# Debug.net
KiCad netlist of a schematic drawn in Altium Designer
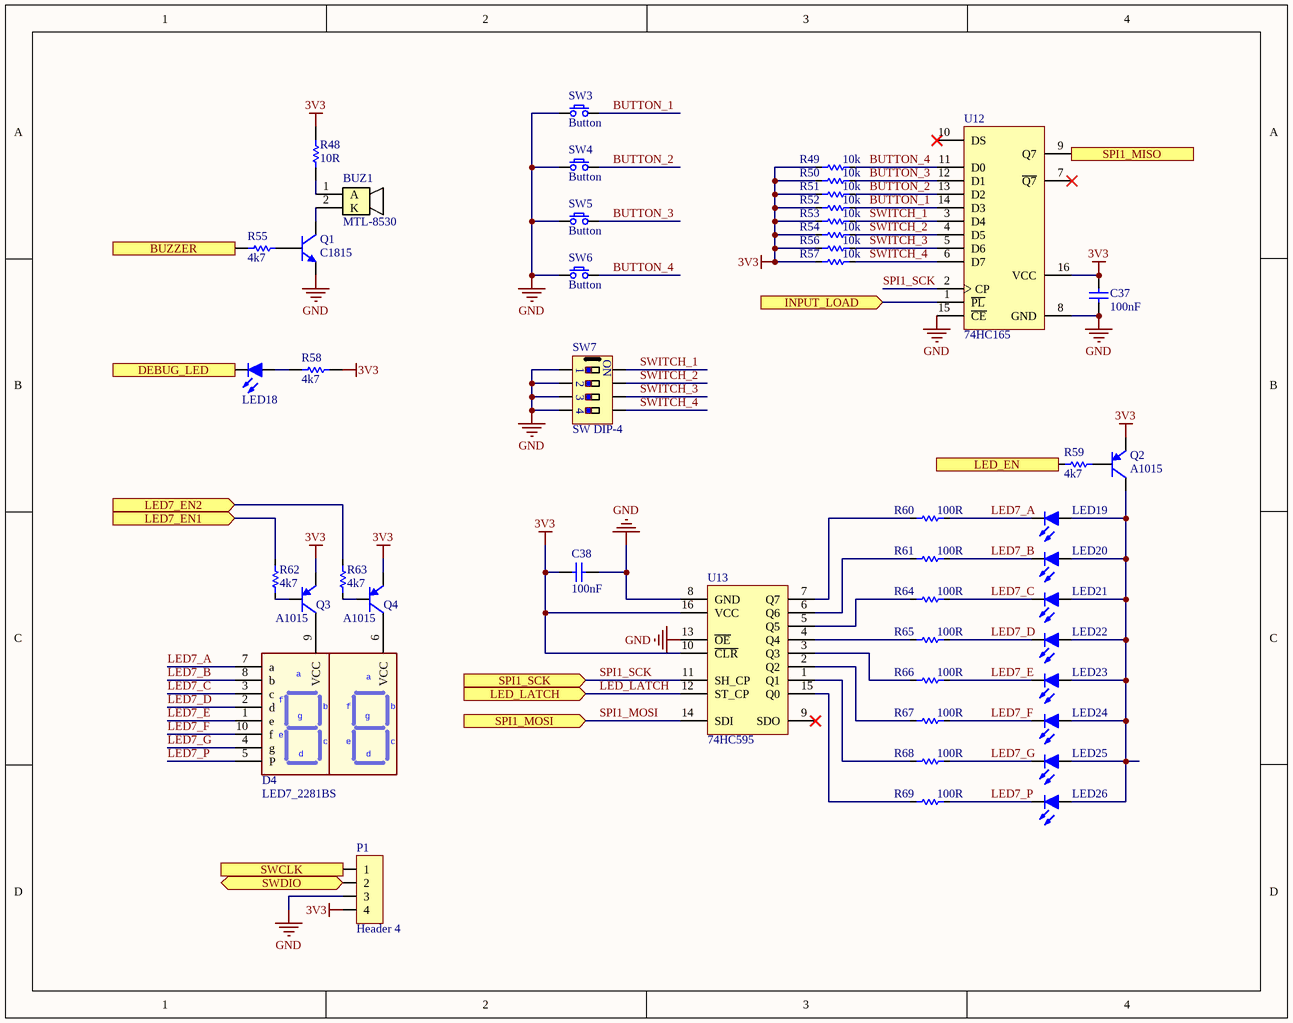
[diagram p0: Debug.SchDoc]

(export (version "E")
  (design (tool "Eeschema 10.0.6"))
  (components
    (comp (ref "BUZ1")
      (value "MTL-8530")
      (footprint "MLT-8530")
      (libsource (lib "BKIT4U_LIB") (part "Buzzer"))
    )
    (comp (ref "C37")
      (value "100nF")
      (footprint "C 0603 (1608)")
      (description "Capacitor non-pol")
      (libsource (lib "BKIT4U_LIB") (part "Capacitor NP"))
    )
    (comp (ref "C38")
      (value "100nF")
      (footprint "C 0603 (1608)")
      (description "Capacitor non-pol")
      (libsource (lib "") (part "Capacitor NP_1"))
    )
    (comp (ref "D4")
      (value "LED7_2281BS")
      (footprint "LED7 2281")
      (libsource (lib "BKIT4U_LIB") (part "LED7_2281BS"))
    )
    (comp (ref "LED18")
      (value "Led-Red")
      (footprint "Led SMD 0603 RED")
      (description "Typical LED")
      (libsource (lib "BKIT4U_LIB") (part "Led"))
    )
    (comp (ref "LED19")
      (value "Led-Red")
      (footprint "Led SMD 0603 RED")
      (description "Typical LED")
      (libsource (lib "BKIT4U_LIB") (part "Led"))
    )
    (comp (ref "LED20")
      (value "Led-Red")
      (footprint "Led SMD 0603 RED")
      (description "Typical LED")
      (libsource (lib "BKIT4U_LIB") (part "Led"))
    )
    (comp (ref "LED21")
      (value "Led-Red")
      (footprint "Led SMD 0603 RED")
      (description "Typical LED")
      (libsource (lib "BKIT4U_LIB") (part "Led"))
    )
    (comp (ref "LED22")
      (value "Led-Red")
      (footprint "Led SMD 0603 RED")
      (description "Typical LED")
      (libsource (lib "BKIT4U_LIB") (part "Led"))
    )
    (comp (ref "LED23")
      (value "Led-Red")
      (footprint "Led SMD 0603 RED")
      (description "Typical LED")
      (libsource (lib "BKIT4U_LIB") (part "Led"))
    )
    (comp (ref "LED24")
      (value "Led-Red")
      (footprint "Led SMD 0603 RED")
      (description "Typical LED")
      (libsource (lib "BKIT4U_LIB") (part "Led"))
    )
    (comp (ref "LED25")
      (value "Led-Red")
      (footprint "Led SMD 0603 RED")
      (description "Typical LED")
      (libsource (lib "BKIT4U_LIB") (part "Led"))
    )
    (comp (ref "LED26")
      (value "Led-Red")
      (footprint "Led SMD 0603 RED")
      (description "Typical LED")
      (libsource (lib "BKIT4U_LIB") (part "Led"))
    )
    (comp (ref "P1")
      (value "Header 4")
      (footprint "Header 4")
      (description "Header, 4-Pin")
      (libsource (lib "BKIT4U_LIB") (part "Header 4"))
    )
    (comp (ref "Q1")
      (value "C1815")
      (footprint "SOT-23")
      (description "NPN Bipolar Transistor")
      (libsource (lib "BKIT4U_LIB") (part "Transistor NPN"))
    )
    (comp (ref "Q2")
      (value "A1015")
      (footprint "SOT-23")
      (description "PNP Bipolar Transistor")
      (fields (field (name "PUBLISHER") "Altium Limited"))
      (libsource (lib "BKIT4U_LIB") (part "Transistor PNP"))
    )
    (comp (ref "Q3")
      (value "A1015")
      (footprint "SOT-23")
      (description "PNP Bipolar Transistor")
      (fields (field (name "PUBLISHER") "Altium Limited"))
      (libsource (lib "BKIT4U_LIB") (part "Transistor PNP"))
    )
    (comp (ref "Q4")
      (value "A1015")
      (footprint "SOT-23")
      (description "PNP Bipolar Transistor")
      (fields (field (name "PUBLISHER") "Altium Limited"))
      (libsource (lib "BKIT4U_LIB") (part "Transistor PNP"))
    )
    (comp (ref "R48")
      (value "10R")
      (footprint "R 0603 (1608)")
      (description "Resistor")
      (fields (field (name "PUBLISHER") "Altium Limited"))
      (libsource (lib "") (part "Resistor_1"))
    )
    (comp (ref "R49")
      (value "10k")
      (footprint "R 0603 (1608)")
      (description "Resistor")
      (fields (field (name "PUBLISHER") "Altium Limited"))
      (libsource (lib "BKIT4U_LIB") (part "Resistor"))
    )
    (comp (ref "R50")
      (value "10k")
      (footprint "R 0603 (1608)")
      (description "Resistor")
      (fields (field (name "PUBLISHER") "Altium Limited"))
      (libsource (lib "BKIT4U_LIB") (part "Resistor"))
    )
    (comp (ref "R51")
      (value "10k")
      (footprint "R 0603 (1608)")
      (description "Resistor")
      (fields (field (name "PUBLISHER") "Altium Limited"))
      (libsource (lib "BKIT4U_LIB") (part "Resistor"))
    )
    (comp (ref "R52")
      (value "10k")
      (footprint "R 0603 (1608)")
      (description "Resistor")
      (fields (field (name "PUBLISHER") "Altium Limited"))
      (libsource (lib "BKIT4U_LIB") (part "Resistor"))
    )
    (comp (ref "R53")
      (value "10k")
      (footprint "R 0603 (1608)")
      (description "Resistor")
      (fields (field (name "PUBLISHER") "Altium Limited"))
      (libsource (lib "BKIT4U_LIB") (part "Resistor"))
    )
    (comp (ref "R54")
      (value "10k")
      (footprint "R 0603 (1608)")
      (description "Resistor")
      (fields (field (name "PUBLISHER") "Altium Limited"))
      (libsource (lib "BKIT4U_LIB") (part "Resistor"))
    )
    (comp (ref "R55")
      (value "4k7")
      (footprint "R 0603 (1608)")
      (description "Resistor")
      (fields (field (name "PUBLISHER") "Altium Limited"))
      (libsource (lib "") (part "Resistor_1"))
    )
    (comp (ref "R56")
      (value "10k")
      (footprint "R 0603 (1608)")
      (description "Resistor")
      (fields (field (name "PUBLISHER") "Altium Limited"))
      (libsource (lib "BKIT4U_LIB") (part "Resistor"))
    )
    (comp (ref "R57")
      (value "10k")
      (footprint "R 0603 (1608)")
      (description "Resistor")
      (fields (field (name "PUBLISHER") "Altium Limited"))
      (libsource (lib "BKIT4U_LIB") (part "Resistor"))
    )
    (comp (ref "R58")
      (value "4k7")
      (footprint "R 0603 (1608)")
      (description "Resistor")
      (fields (field (name "PUBLISHER") "Altium Limited"))
      (libsource (lib "") (part "Resistor_1"))
    )
    (comp (ref "R59")
      (value "4k7")
      (footprint "R 0603 (1608)")
      (description "Resistor")
      (fields (field (name "PUBLISHER") "Altium Limited"))
      (libsource (lib "BKIT4U_LIB") (part "Resistor"))
    )
    (comp (ref "R60")
      (value "100R")
      (footprint "R 0603 (1608)")
      (description "Resistor")
      (fields (field (name "PUBLISHER") "Altium Limited"))
      (libsource (lib "BKIT4U_LIB") (part "Resistor"))
    )
    (comp (ref "R61")
      (value "100R")
      (footprint "R 0603 (1608)")
      (description "Resistor")
      (fields (field (name "PUBLISHER") "Altium Limited"))
      (libsource (lib "BKIT4U_LIB") (part "Resistor"))
    )
    (comp (ref "R62")
      (value "4k7")
      (footprint "R 0603 (1608)")
      (description "Resistor")
      (fields (field (name "PUBLISHER") "Altium Limited"))
      (libsource (lib "BKIT4U_LIB") (part "Resistor"))
    )
    (comp (ref "R63")
      (value "4k7")
      (footprint "R 0603 (1608)")
      (description "Resistor")
      (fields (field (name "PUBLISHER") "Altium Limited"))
      (libsource (lib "BKIT4U_LIB") (part "Resistor"))
    )
    (comp (ref "R64")
      (value "100R")
      (footprint "R 0603 (1608)")
      (description "Resistor")
      (fields (field (name "PUBLISHER") "Altium Limited"))
      (libsource (lib "BKIT4U_LIB") (part "Resistor"))
    )
    (comp (ref "R65")
      (value "100R")
      (footprint "R 0603 (1608)")
      (description "Resistor")
      (fields (field (name "PUBLISHER") "Altium Limited"))
      (libsource (lib "BKIT4U_LIB") (part "Resistor"))
    )
    (comp (ref "R66")
      (value "100R")
      (footprint "R 0603 (1608)")
      (description "Resistor")
      (fields (field (name "PUBLISHER") "Altium Limited"))
      (libsource (lib "BKIT4U_LIB") (part "Resistor"))
    )
    (comp (ref "R67")
      (value "100R")
      (footprint "R 0603 (1608)")
      (description "Resistor")
      (fields (field (name "PUBLISHER") "Altium Limited"))
      (libsource (lib "BKIT4U_LIB") (part "Resistor"))
    )
    (comp (ref "R68")
      (value "100R")
      (footprint "R 0603 (1608)")
      (description "Resistor")
      (fields (field (name "PUBLISHER") "Altium Limited"))
      (libsource (lib "BKIT4U_LIB") (part "Resistor"))
    )
    (comp (ref "R69")
      (value "100R")
      (footprint "R 0603 (1608)")
      (description "Resistor")
      (fields (field (name "PUBLISHER") "Altium Limited"))
      (libsource (lib "BKIT4U_LIB") (part "Resistor"))
    )
    (comp (ref "SW3")
      (value "Button")
      (footprint "SW/2/SMD - 6X6X5")
      (description "Tact switch 2 pin")
      (libsource (lib "BKIT4U_LIB") (part "SW SPST"))
    )
    (comp (ref "SW4")
      (value "Button")
      (footprint "SW/2/SMD - 6X6X5")
      (description "Tact switch 2 pin")
      (libsource (lib "BKIT4U_LIB") (part "SW SPST"))
    )
    (comp (ref "SW5")
      (value "Button")
      (footprint "SW/2/SMD - 6X6X5")
      (description "Tact switch 2 pin")
      (libsource (lib "BKIT4U_LIB") (part "SW SPST"))
    )
    (comp (ref "SW6")
      (value "Button")
      (footprint "SW/2/SMD - 6X6X5")
      (description "Tact switch 2 pin")
      (libsource (lib "BKIT4U_LIB") (part "SW SPST"))
    )
    (comp (ref "SW7")
      (value "SW DIP-4")
      (footprint "SW/DIP4")
      (libsource (lib "BKIT4U_LIB") (part "SW DIP-4"))
    )
    (comp (ref "U12")
      (value "74HC165")
      (footprint "TSSOP 16 65P")
      (description "8-bit serial-in, serial or parallel-out  shift register with output latches;  3-state")
      (libsource (lib "BKIT4U_LIB") (part "74HC165"))
    )
    (comp (ref "U13")
      (value "74HC595")
      (footprint "TSSOP 16 65P")
      (description "8-bit serial-in, serial or parallel-out  shift register with output latches;  3-state")
      (libsource (lib "BKIT4U_LIB") (part "74HC595"))
    )
  )
  (nets
    (net (code "1") (name "/BUTTON_1") (class "Default")
      (node (ref "R52") (pin "2") (pinfunction "2_2") (pintype "passive"))
      (node (ref "SW3") (pin "2") (pinfunction "2_2") (pintype "passive"))
      (node (ref "U12") (pin "14") (pinfunction "D3_14") (pintype "passive"))
    )
    (net (code "2") (name "/BUTTON_2") (class "Default")
      (node (ref "R51") (pin "2") (pinfunction "2_2") (pintype "passive"))
      (node (ref "SW4") (pin "2") (pinfunction "2_2") (pintype "passive"))
      (node (ref "U12") (pin "13") (pinfunction "D2_13") (pintype "passive"))
    )
    (net (code "3") (name "/BUTTON_3") (class "Default")
      (node (ref "R50") (pin "2") (pinfunction "2_2") (pintype "passive"))
      (node (ref "SW5") (pin "2") (pinfunction "2_2") (pintype "passive"))
      (node (ref "U12") (pin "12") (pinfunction "D1_12") (pintype "passive"))
    )
    (net (code "4") (name "/BUTTON_4") (class "Default")
      (node (ref "R49") (pin "2") (pinfunction "2_2") (pintype "passive"))
      (node (ref "SW6") (pin "2") (pinfunction "2_2") (pintype "passive"))
      (node (ref "U12") (pin "11") (pinfunction "D0_11") (pintype "passive"))
    )
    (net (code "5") (name "/BUZZER") (class "Default")
      (node (ref "R55") (pin "1") (pinfunction "1_1") (pintype "passive"))
    )
    (net (code "6") (name "/DEBUG_LED") (class "Default")
      (node (ref "LED18") (pin "2") (pinfunction "K_2") (pintype "passive"))
    )
    (net (code "7") (name "/INPUT_LOAD") (class "Default")
      (node (ref "U12") (pin "1") (pinfunction "~{PL}_1") (pintype "passive"))
    )
    (net (code "8") (name "/LED7_A") (class "Default")
      (node (ref "D4") (pin "7") (pinfunction "a_7") (pintype "passive"))
      (node (ref "LED19") (pin "2") (pinfunction "K_2") (pintype "passive"))
      (node (ref "R60") (pin "2") (pinfunction "2_2") (pintype "passive"))
    )
    (net (code "9") (name "/LED7_B") (class "Default")
      (node (ref "D4") (pin "8") (pinfunction "b_8") (pintype "passive"))
      (node (ref "LED20") (pin "2") (pinfunction "K_2") (pintype "passive"))
      (node (ref "R61") (pin "2") (pinfunction "2_2") (pintype "passive"))
    )
    (net (code "10") (name "/LED7_C") (class "Default")
      (node (ref "D4") (pin "3") (pinfunction "c_3") (pintype "passive"))
      (node (ref "LED21") (pin "2") (pinfunction "K_2") (pintype "passive"))
      (node (ref "R64") (pin "2") (pinfunction "2_2") (pintype "passive"))
    )
    (net (code "11") (name "/LED7_D") (class "Default")
      (node (ref "D4") (pin "2") (pinfunction "d_2") (pintype "passive"))
      (node (ref "LED22") (pin "2") (pinfunction "K_2") (pintype "passive"))
      (node (ref "R65") (pin "2") (pinfunction "2_2") (pintype "passive"))
    )
    (net (code "12") (name "/LED7_E") (class "Default")
      (node (ref "D4") (pin "1") (pinfunction "e_1") (pintype "passive"))
      (node (ref "LED23") (pin "2") (pinfunction "K_2") (pintype "passive"))
      (node (ref "R66") (pin "2") (pinfunction "2_2") (pintype "passive"))
    )
    (net (code "13") (name "/LED7_EN1") (class "Default")
      (node (ref "R62") (pin "2") (pinfunction "2_2") (pintype "passive"))
    )
    (net (code "14") (name "/LED7_EN2") (class "Default")
      (node (ref "R63") (pin "2") (pinfunction "2_2") (pintype "passive"))
    )
    (net (code "15") (name "/LED7_F") (class "Default")
      (node (ref "D4") (pin "10") (pinfunction "f_10") (pintype "passive"))
      (node (ref "LED24") (pin "2") (pinfunction "K_2") (pintype "passive"))
      (node (ref "R67") (pin "2") (pinfunction "2_2") (pintype "passive"))
    )
    (net (code "16") (name "/LED7_G") (class "Default")
      (node (ref "D4") (pin "4") (pinfunction "g_4") (pintype "passive"))
      (node (ref "LED25") (pin "2") (pinfunction "K_2") (pintype "passive"))
      (node (ref "R68") (pin "2") (pinfunction "2_2") (pintype "passive"))
    )
    (net (code "17") (name "/LED7_P") (class "Default")
      (node (ref "D4") (pin "5") (pinfunction "P_5") (pintype "passive"))
      (node (ref "LED26") (pin "2") (pinfunction "K_2") (pintype "passive"))
      (node (ref "R69") (pin "2") (pinfunction "2_2") (pintype "passive"))
    )
    (net (code "18") (name "/LED_EN") (class "Default")
      (node (ref "R59") (pin "2") (pinfunction "2_2") (pintype "passive"))
    )
    (net (code "19") (name "/LED_LATCH") (class "Default")
      (node (ref "U13") (pin "12") (pinfunction "ST_CP_12") (pintype "passive"))
    )
    (net (code "20") (name "/SPI1_MISO") (class "Default")
      (node (ref "U12") (pin "9") (pinfunction "Q7_9") (pintype "passive"))
    )
    (net (code "21") (name "/SPI1_MOSI") (class "Default")
      (node (ref "U13") (pin "14") (pinfunction "SDI_14") (pintype "passive"))
    )
    (net (code "22") (name "/SPI1_SCK") (class "Default")
      (node (ref "U12") (pin "2") (pinfunction "CP_2") (pintype "passive"))
      (node (ref "U13") (pin "11") (pinfunction "SH_CP_11") (pintype "passive"))
    )
    (net (code "23") (name "/SWCLK") (class "Default")
      (node (ref "P1") (pin "1") (pinfunction "1_1") (pintype "passive"))
    )
    (net (code "24") (name "/SWDIO") (class "Default")
      (node (ref "P1") (pin "2") (pinfunction "2_2") (pintype "passive"))
    )
    (net (code "25") (name "/SWITCH_1") (class "Default")
      (node (ref "R53") (pin "2") (pinfunction "2_2") (pintype "passive"))
      (node (ref "SW7") (pin "8") (pinfunction "8_8") (pintype "passive"))
      (node (ref "U12") (pin "3") (pinfunction "D4_3") (pintype "passive"))
    )
    (net (code "26") (name "/SWITCH_2") (class "Default")
      (node (ref "R54") (pin "2") (pinfunction "2_2") (pintype "passive"))
      (node (ref "SW7") (pin "7") (pinfunction "7_7") (pintype "passive"))
      (node (ref "U12") (pin "4") (pinfunction "D5_4") (pintype "passive"))
    )
    (net (code "27") (name "/SWITCH_3") (class "Default")
      (node (ref "R56") (pin "2") (pinfunction "2_2") (pintype "passive"))
      (node (ref "SW7") (pin "6") (pinfunction "6_6") (pintype "passive"))
      (node (ref "U12") (pin "5") (pinfunction "D6_5") (pintype "passive"))
    )
    (net (code "28") (name "/SWITCH_4") (class "Default")
      (node (ref "R57") (pin "2") (pinfunction "2_2") (pintype "passive"))
      (node (ref "SW7") (pin "5") (pinfunction "5_5") (pintype "passive"))
      (node (ref "U12") (pin "6") (pinfunction "D7_6") (pintype "passive"))
    )
    (net (code "29") (name "3V3") (class "Default")
      (node (ref "C37") (pin "1") (pinfunction "1_1") (pintype "passive"))
      (node (ref "C38") (pin "1") (pinfunction "1_1") (pintype "passive"))
      (node (ref "P1") (pin "4") (pinfunction "4_4") (pintype "passive"))
      (node (ref "Q2") (pin "2") (pinfunction "E_2") (pintype "passive"))
      (node (ref "Q3") (pin "2") (pinfunction "E_2") (pintype "passive"))
      (node (ref "Q4") (pin "2") (pinfunction "E_2") (pintype "passive"))
      (node (ref "R48") (pin "2") (pinfunction "2_2") (pintype "passive"))
      (node (ref "R49") (pin "1") (pinfunction "1_1") (pintype "passive"))
      (node (ref "R50") (pin "1") (pinfunction "1_1") (pintype "passive"))
      (node (ref "R51") (pin "1") (pinfunction "1_1") (pintype "passive"))
      (node (ref "R52") (pin "1") (pinfunction "1_1") (pintype "passive"))
      (node (ref "R53") (pin "1") (pinfunction "1_1") (pintype "passive"))
      (node (ref "R54") (pin "1") (pinfunction "1_1") (pintype "passive"))
      (node (ref "R56") (pin "1") (pinfunction "1_1") (pintype "passive"))
      (node (ref "R57") (pin "1") (pinfunction "1_1") (pintype "passive"))
      (node (ref "R58") (pin "2") (pinfunction "2_2") (pintype "passive"))
      (node (ref "U12") (pin "16") (pinfunction "VCC_16") (pintype "passive"))
      (node (ref "U13") (pin "10") (pinfunction "~{CLR}_10") (pintype "passive"))
      (node (ref "U13") (pin "16") (pinfunction "VCC_16") (pintype "passive"))
    )
    (net (code "30") (name "GND") (class "Default")
      (node (ref "C37") (pin "2") (pinfunction "2_2") (pintype "passive"))
      (node (ref "C38") (pin "2") (pinfunction "2_2") (pintype "passive"))
      (node (ref "P1") (pin "3") (pinfunction "3_3") (pintype "passive"))
      (node (ref "Q1") (pin "2") (pinfunction "E_2") (pintype "passive"))
      (node (ref "SW3") (pin "1") (pinfunction "1_1") (pintype "passive"))
      (node (ref "SW4") (pin "1") (pinfunction "1_1") (pintype "passive"))
      (node (ref "SW5") (pin "1") (pinfunction "1_1") (pintype "passive"))
      (node (ref "SW6") (pin "1") (pinfunction "1_1") (pintype "passive"))
      (node (ref "SW7") (pin "1") (pinfunction "1_1") (pintype "passive"))
      (node (ref "SW7") (pin "2") (pinfunction "2_2") (pintype "passive"))
      (node (ref "SW7") (pin "3") (pinfunction "3_3") (pintype "passive"))
      (node (ref "SW7") (pin "4") (pinfunction "4_4") (pintype "passive"))
      (node (ref "U12") (pin "15") (pinfunction "~{CE}_15") (pintype "passive"))
      (node (ref "U12") (pin "8") (pinfunction "GND_8") (pintype "passive"))
      (node (ref "U13") (pin "13") (pinfunction "~{OE}_13") (pintype "passive"))
      (node (ref "U13") (pin "8") (pinfunction "GND_8") (pintype "passive"))
    )
    (net (code "31") (name "Net-(BUZ1-A)") (class "Default")
      (node (ref "BUZ1") (pin "1") (pinfunction "A_1") (pintype "passive"))
      (node (ref "R48") (pin "1") (pinfunction "1_1") (pintype "passive"))
    )
    (net (code "32") (name "Net-(BUZ1-K)") (class "Default")
      (node (ref "BUZ1") (pin "2") (pinfunction "K_2") (pintype "passive"))
      (node (ref "Q1") (pin "3") (pinfunction "C_3") (pintype "passive"))
    )
    (net (code "33") (name "Net-(LED18-A)") (class "Default")
      (node (ref "LED18") (pin "1") (pinfunction "A_1") (pintype "passive"))
      (node (ref "R58") (pin "1") (pinfunction "1_1") (pintype "passive"))
    )
    (net (code "34") (name "Net-(LED19-A)") (class "Default")
      (node (ref "LED19") (pin "1") (pinfunction "A_1") (pintype "passive"))
      (node (ref "LED20") (pin "1") (pinfunction "A_1") (pintype "passive"))
      (node (ref "LED21") (pin "1") (pinfunction "A_1") (pintype "passive"))
      (node (ref "LED22") (pin "1") (pinfunction "A_1") (pintype "passive"))
      (node (ref "LED23") (pin "1") (pinfunction "A_1") (pintype "passive"))
      (node (ref "LED24") (pin "1") (pinfunction "A_1") (pintype "passive"))
      (node (ref "LED25") (pin "1") (pinfunction "A_1") (pintype "passive"))
      (node (ref "LED26") (pin "1") (pinfunction "A_1") (pintype "passive"))
      (node (ref "Q2") (pin "3") (pinfunction "C_3") (pintype "passive"))
    )
    (net (code "35") (name "Net-(Q1-B)") (class "Default")
      (node (ref "Q1") (pin "1") (pinfunction "B_1") (pintype "passive"))
      (node (ref "R55") (pin "2") (pinfunction "2_2") (pintype "passive"))
    )
    (net (code "36") (name "Net-(Q2-B)") (class "Default")
      (node (ref "Q2") (pin "1") (pinfunction "B_1") (pintype "passive"))
      (node (ref "R59") (pin "1") (pinfunction "1_1") (pintype "passive"))
    )
    (net (code "37") (name "Net-(Q3-B)") (class "Default")
      (node (ref "Q3") (pin "1") (pinfunction "B_1") (pintype "passive"))
      (node (ref "R62") (pin "1") (pinfunction "1_1") (pintype "passive"))
    )
    (net (code "38") (name "Net-(Q3-C)") (class "Default")
      (node (ref "D4") (pin "9") (pinfunction "VCC_9") (pintype "passive"))
      (node (ref "Q3") (pin "3") (pinfunction "C_3") (pintype "passive"))
    )
    (net (code "39") (name "Net-(Q4-B)") (class "Default")
      (node (ref "Q4") (pin "1") (pinfunction "B_1") (pintype "passive"))
      (node (ref "R63") (pin "1") (pinfunction "1_1") (pintype "passive"))
    )
    (net (code "40") (name "Net-(Q4-C)") (class "Default")
      (node (ref "D4") (pin "6") (pinfunction "VCC_6") (pintype "passive"))
      (node (ref "Q4") (pin "3") (pinfunction "C_3") (pintype "passive"))
    )
    (net (code "41") (name "Net-(U13-Q0)") (class "Default")
      (node (ref "R69") (pin "1") (pinfunction "1_1") (pintype "passive"))
      (node (ref "U13") (pin "15") (pinfunction "Q0_15") (pintype "passive"))
    )
    (net (code "42") (name "Net-(U13-Q1)") (class "Default")
      (node (ref "R68") (pin "1") (pinfunction "1_1") (pintype "passive"))
      (node (ref "U13") (pin "1") (pinfunction "Q1_1") (pintype "passive"))
    )
    (net (code "43") (name "Net-(U13-Q2)") (class "Default")
      (node (ref "R67") (pin "1") (pinfunction "1_1") (pintype "passive"))
      (node (ref "U13") (pin "2") (pinfunction "Q2_2") (pintype "passive"))
    )
    (net (code "44") (name "Net-(U13-Q3)") (class "Default")
      (node (ref "R66") (pin "1") (pinfunction "1_1") (pintype "passive"))
      (node (ref "U13") (pin "3") (pinfunction "Q3_3") (pintype "passive"))
    )
    (net (code "45") (name "Net-(U13-Q4)") (class "Default")
      (node (ref "R65") (pin "1") (pinfunction "1_1") (pintype "passive"))
      (node (ref "U13") (pin "4") (pinfunction "Q4_4") (pintype "passive"))
    )
    (net (code "46") (name "Net-(U13-Q5)") (class "Default")
      (node (ref "R64") (pin "1") (pinfunction "1_1") (pintype "passive"))
      (node (ref "U13") (pin "5") (pinfunction "Q5_5") (pintype "passive"))
    )
    (net (code "47") (name "Net-(U13-Q6)") (class "Default")
      (node (ref "R61") (pin "1") (pinfunction "1_1") (pintype "passive"))
      (node (ref "U13") (pin "6") (pinfunction "Q6_6") (pintype "passive"))
    )
    (net (code "48") (name "Net-(U13-Q7)") (class "Default")
      (node (ref "R60") (pin "1") (pinfunction "1_1") (pintype "passive"))
      (node (ref "U13") (pin "7") (pinfunction "Q7_7") (pintype "passive"))
    )
    (net (code "49") (name "unconnected-(U12-DS-Pad10)") (class "Default")
      (node (ref "U12") (pin "10") (pinfunction "DS_10") (pintype "passive+no_connect"))
    )
    (net (code "50") (name "unconnected-(U12-~{Q7}-Pad7)") (class "Default")
      (node (ref "U12") (pin "7") (pinfunction "~{Q7}_7") (pintype "passive+no_connect"))
    )
    (net (code "51") (name "unconnected-(U13-SDO-Pad9)") (class "Default")
      (node (ref "U13") (pin "9") (pinfunction "SDO_9") (pintype "passive+no_connect"))
    )
  )
)
